# Board.net
KiCad netlist of a schematic drawn in EAGLE
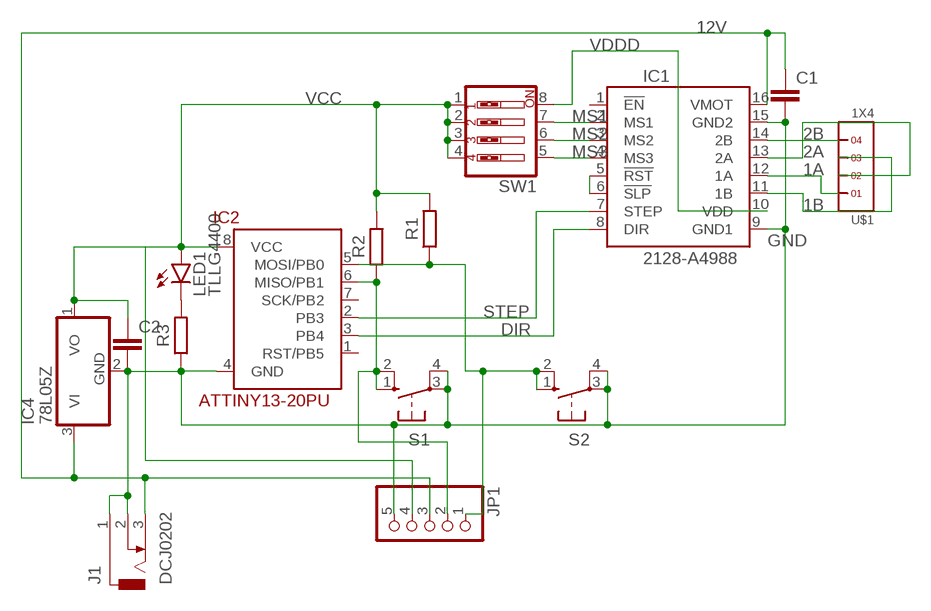
[diagram p0: schematic, sheet 1]

(export (version "E")
  (design (tool "Eeschema 10.0.6"))
  (components
    (comp (ref "C1")
      (value "C2.5/6")
      (footprint "eagle-import:C2.5-6")
      (libsource (lib "eagle-import") (part "C2.5/6"))
    )
    (comp (ref "C2")
      (value "C2.5/6")
      (footprint "eagle-import:C2.5-6")
      (libsource (lib "eagle-import") (part "C2.5/6"))
    )
    (comp (ref "IC1")
      (value "2128-A4988")
      (footprint "eagle-import:A4988")
      (libsource (lib "eagle-import") (part "2128-A4988"))
    )
    (comp (ref "IC2")
      (value "ATTINY13-20PU")
      (footprint "eagle-import:DIL08")
      (libsource (lib "eagle-import") (part "ATTINY13-20PU"))
    )
    (comp (ref "IC4")
      (value "78L05Z")
      (footprint "eagle-import:TO92")
      (libsource (lib "eagle-import") (part "78ZL05"))
    )
    (comp (ref "J1")
      (value "DCJ0202")
      (footprint "eagle-import:DCJ0202")
      (libsource (lib "eagle-import") (part "DCJ0202"))
    )
    (comp (ref "JP1")
      (value "PINHD-1X5")
      (footprint "eagle-import:1X05")
      (libsource (lib "eagle-import") (part "PINHD-1X5"))
    )
    (comp (ref "LED1")
      (value "TLLG4400")
      (footprint "eagle-import:LED3MM")
      (fields (field (name "MF") "VISHAY SEMICONDUCTOR"))
      (libsource (lib "eagle-import") (part "TLLG4400"))
    )
    (comp (ref "R1")
      (value "R_AXIAL-7.2MM-PITCH")
      (footprint "eagle-import:RESAD724W46L381D178B")
      (libsource (lib "eagle-import") (part "RAXIAL-7.2MM-PITCH_"))
    )
    (comp (ref "R2")
      (value "R_AXIAL-7.2MM-PITCH")
      (footprint "eagle-import:RESAD724W46L381D178B")
      (libsource (lib "eagle-import") (part "RAXIAL-7.2MM-PITCH_"))
    )
    (comp (ref "R3")
      (value "R_AXIAL-7.2MM-PITCH")
      (footprint "eagle-import:RESAD724W46L381D178B")
      (libsource (lib "eagle-import") (part "RAXIAL-7.2MM-PITCH_"))
    )
    (comp (ref "S1")
      (value "10-XX")
      (footprint "eagle-import:B3F-10XX")
      (fields (field (name "MPN") "B3F-1000"))
      (libsource (lib "eagle-import") (part "10-XX"))
    )
    (comp (ref "S2")
      (value "10-XX")
      (footprint "eagle-import:B3F-10XX")
      (fields (field (name "MPN") "B3F-1000"))
      (libsource (lib "eagle-import") (part "10-XX"))
    )
    (comp (ref "SW1")
      (value "SW_DIP-4")
      (footprint "eagle-import:EDG-04")
      (libsource (lib "eagle-import") (part "SW_DIP-4"))
    )
    (comp (ref "U$1")
      (value "1X4")
      (footprint "eagle-import:1X4")
      (libsource (lib "eagle-import") (part "1X4"))
    )
  )
  (nets
    (net (code "1") (name "/1A") (class "Default")
      (node (ref "IC1") (pin "12") (pinfunction "1A_12") (pintype "output"))
      (node (ref "U$1") (pin "1") (pinfunction "1_1") (pintype "bidirectional"))
    )
    (net (code "2") (name "/1B") (class "Default")
      (node (ref "IC1") (pin "11") (pinfunction "1B_11") (pintype "output"))
      (node (ref "U$1") (pin "3") (pinfunction "3_3") (pintype "bidirectional"))
    )
    (net (code "3") (name "/2A") (class "Default")
      (node (ref "IC1") (pin "13") (pinfunction "2A_13") (pintype "output"))
      (node (ref "U$1") (pin "2") (pinfunction "2_2") (pintype "bidirectional"))
    )
    (net (code "4") (name "/2B") (class "Default")
      (node (ref "IC1") (pin "14") (pinfunction "2B_14") (pintype "output"))
      (node (ref "U$1") (pin "4") (pinfunction "4_4") (pintype "bidirectional"))
    )
    (net (code "5") (name "/12V") (class "Default")
      (node (ref "C1") (pin "1") (pinfunction "1_1") (pintype "passive"))
      (node (ref "IC1") (pin "16") (pinfunction "VMOT_16") (pintype "power_in"))
      (node (ref "IC4") (pin "3") (pinfunction "VI_3") (pintype "input"))
      (node (ref "J1") (pin "3") (pinfunction "3_3") (pintype "passive"))
      (node (ref "JP1") (pin "3") (pinfunction "3_3") (pintype "passive"))
    )
    (net (code "6") (name "/DIR") (class "Default")
      (node (ref "IC1") (pin "8") (pinfunction "DIR_8") (pintype "input"))
      (node (ref "IC2") (pin "3") (pinfunction "PB4_3") (pintype "bidirectional"))
    )
    (net (code "7") (name "/GND") (class "Default")
      (node (ref "C1") (pin "2") (pinfunction "2_2") (pintype "passive"))
      (node (ref "C2") (pin "2") (pinfunction "2_2") (pintype "passive"))
      (node (ref "IC1") (pin "15") (pinfunction "GND2_15") (pintype "power_in"))
      (node (ref "IC1") (pin "9") (pinfunction "GND1_9") (pintype "power_in"))
      (node (ref "IC2") (pin "4") (pinfunction "GND_4") (pintype "power_in"))
      (node (ref "IC4") (pin "2") (pinfunction "GND_2") (pintype "passive"))
      (node (ref "J1") (pin "1") (pinfunction "1_1") (pintype "passive"))
      (node (ref "J1") (pin "2") (pinfunction "2_2") (pintype "passive"))
      (node (ref "JP1") (pin "5") (pinfunction "5_5") (pintype "passive"))
      (node (ref "R3") (pin "1") (pinfunction "1_1") (pintype "passive"))
      (node (ref "S1") (pin "3") (pinfunction "P_3") (pintype "passive"))
      (node (ref "S1") (pin "4") (pinfunction "P1_4") (pintype "passive"))
      (node (ref "S2") (pin "3") (pinfunction "P_3") (pintype "passive"))
      (node (ref "S2") (pin "4") (pinfunction "P1_4") (pintype "passive"))
    )
    (net (code "8") (name "/MS1") (class "Default")
      (node (ref "IC1") (pin "2") (pinfunction "MS1_2") (pintype "passive"))
      (node (ref "SW1") (pin "7") (pinfunction "7_7") (pintype "passive"))
    )
    (net (code "9") (name "/MS2") (class "Default")
      (node (ref "IC1") (pin "3") (pinfunction "MS2_3") (pintype "passive"))
      (node (ref "SW1") (pin "6") (pinfunction "6_6") (pintype "passive"))
    )
    (net (code "10") (name "/MS3") (class "Default")
      (node (ref "IC1") (pin "4") (pinfunction "MS3_4") (pintype "passive"))
      (node (ref "SW1") (pin "5") (pinfunction "5_5") (pintype "passive"))
    )
    (net (code "11") (name "/STEP") (class "Default")
      (node (ref "IC1") (pin "7") (pinfunction "STEP_7") (pintype "input"))
      (node (ref "IC2") (pin "2") (pinfunction "PB3_2") (pintype "bidirectional"))
    )
    (net (code "12") (name "/VCC") (class "Default")
      (node (ref "C2") (pin "1") (pinfunction "1_1") (pintype "passive"))
      (node (ref "IC2") (pin "8") (pinfunction "VCC_8") (pintype "power_in"))
      (node (ref "IC4") (pin "1") (pinfunction "VO_1") (pintype "passive"))
      (node (ref "JP1") (pin "4") (pinfunction "4_4") (pintype "passive"))
      (node (ref "LED1") (pin "A") (pinfunction "A_A") (pintype "passive"))
      (node (ref "R1") (pin "2") (pinfunction "2_2") (pintype "passive"))
      (node (ref "R2") (pin "2") (pinfunction "2_2") (pintype "passive"))
      (node (ref "SW1") (pin "1") (pinfunction "1_1") (pintype "passive"))
      (node (ref "SW1") (pin "2") (pinfunction "2_2") (pintype "passive"))
      (node (ref "SW1") (pin "3") (pinfunction "3_3") (pintype "passive"))
      (node (ref "SW1") (pin "4") (pinfunction "4_4") (pintype "passive"))
    )
    (net (code "13") (name "/VDDD") (class "Default")
      (node (ref "IC1") (pin "10") (pinfunction "VDD_10") (pintype "power_in"))
      (node (ref "SW1") (pin "8") (pinfunction "8_8") (pintype "passive"))
    )
    (net (code "14") (name "Net-(IC1-~{RST})") (class "Default")
      (node (ref "IC1") (pin "5") (pinfunction "~{RST}_5") (pintype "passive"))
      (node (ref "IC1") (pin "6") (pinfunction "~{SLP}_6") (pintype "passive"))
    )
    (net (code "15") (name "Net-(IC2-MISO{slash}PB1)") (class "Default")
      (node (ref "IC2") (pin "6") (pinfunction "MISO/PB1_6") (pintype "bidirectional"))
      (node (ref "JP1") (pin "2") (pinfunction "2_2") (pintype "passive"))
      (node (ref "R2") (pin "1") (pinfunction "1_1") (pintype "passive"))
      (node (ref "S1") (pin "1") (pinfunction "S_1") (pintype "passive"))
      (node (ref "S1") (pin "2") (pinfunction "S1_2") (pintype "passive"))
    )
    (net (code "16") (name "Net-(IC2-MOSI{slash}PB0)") (class "Default")
      (node (ref "IC2") (pin "5") (pinfunction "MOSI/PB0_5") (pintype "bidirectional"))
      (node (ref "JP1") (pin "1") (pinfunction "1_1") (pintype "passive"))
      (node (ref "R1") (pin "1") (pinfunction "1_1") (pintype "passive"))
      (node (ref "S2") (pin "1") (pinfunction "S_1") (pintype "passive"))
      (node (ref "S2") (pin "2") (pinfunction "S1_2") (pintype "passive"))
    )
    (net (code "17") (name "Net-(LED1-C)") (class "Default")
      (node (ref "LED1") (pin "K") (pinfunction "C_K") (pintype "passive"))
      (node (ref "R3") (pin "2") (pinfunction "2_2") (pintype "passive"))
    )
    (net (code "18") (name "unconnected-(IC1-~{EN}-Pad1)") (class "Default")
      (node (ref "IC1") (pin "1") (pinfunction "~{EN}_1") (pintype "passive"))
    )
    (net (code "19") (name "unconnected-(IC2-RST{slash}PB5-Pad1)") (class "Default")
      (node (ref "IC2") (pin "1") (pinfunction "RST/PB5_1") (pintype "bidirectional"))
    )
    (net (code "20") (name "unconnected-(IC2-SCK{slash}PB2-Pad7)") (class "Default")
      (node (ref "IC2") (pin "7") (pinfunction "SCK/PB2_7") (pintype "bidirectional"))
    )
  )
)
